# SC4541.net
KiCad netlist of a schematic drawn in EAGLE
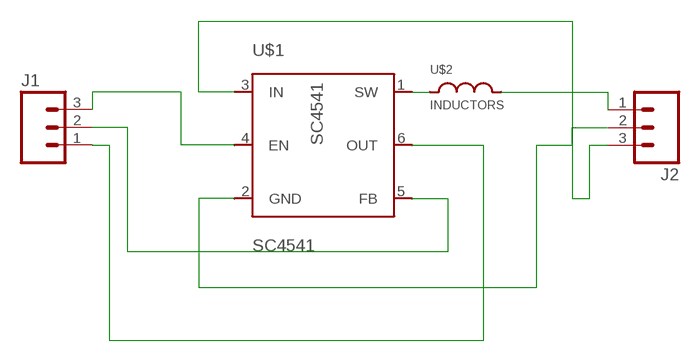
[diagram p0: schematic, sheet 1]

(export (version "E")
  (design (tool "Eeschema 10.0.6"))
  (components
    (comp (ref "J1")
      (value "M03PTH")
      (footprint "eagle-import:1X03")
      (libsource (lib "eagle-import") (part "M03PTH"))
    )
    (comp (ref "J2")
      (value "M03PTH")
      (footprint "eagle-import:1X03")
      (libsource (lib "eagle-import") (part "M03PTH"))
    )
    (comp (ref "U$1")
      (value "SC4541")
      (footprint "eagle-import:SOT23-6")
      (libsource (lib "eagle-import") (part "SC4541"))
    )
    (comp (ref "U$2")
      (value "INDUCTORS")
      (footprint "eagle-import:1212_3X3")
      (libsource (lib "eagle-import") (part "INDUCTORS"))
    )
  )
  (nets
    (net (code "1") (name "Net-(J2-Pad1)") (class "Default")
      (node (ref "J2") (pin "1") (pinfunction "1_1") (pintype "passive"))
      (node (ref "U$2") (pin "P$1") (pinfunction "P$1_P$1") (pintype "passive"))
    )
    (net (code "2") (name "Net-(U$1-EN)") (class "Default")
      (node (ref "J1") (pin "3") (pinfunction "3_3") (pintype "passive"))
      (node (ref "U$1") (pin "4") (pinfunction "EN_4") (pintype "input"))
    )
    (net (code "3") (name "Net-(U$1-FB)") (class "Default")
      (node (ref "J1") (pin "2") (pinfunction "2_2") (pintype "passive"))
      (node (ref "U$1") (pin "5") (pinfunction "FB_5") (pintype "input"))
    )
    (net (code "4") (name "Net-(U$1-GND)") (class "Default")
      (node (ref "J2") (pin "2") (pinfunction "2_2") (pintype "passive"))
      (node (ref "U$1") (pin "2") (pinfunction "GND_2") (pintype "power_in"))
    )
    (net (code "5") (name "Net-(U$1-IN)") (class "Default")
      (node (ref "J2") (pin "3") (pinfunction "3_3") (pintype "passive"))
      (node (ref "U$1") (pin "3") (pinfunction "IN_3") (pintype "input"))
    )
    (net (code "6") (name "Net-(U$1-OUT)") (class "Default")
      (node (ref "J1") (pin "1") (pinfunction "1_1") (pintype "passive"))
      (node (ref "U$1") (pin "6") (pinfunction "OUT_6") (pintype "output"))
    )
    (net (code "7") (name "Net-(U$1-SW)") (class "Default")
      (node (ref "U$1") (pin "1") (pinfunction "SW_1") (pintype "bidirectional"))
      (node (ref "U$2") (pin "P$2") (pinfunction "P$2_P$2") (pintype "passive"))
    )
  )
)
